# PROC010C_LP_Connector.net
KiCad netlist of a schematic drawn in Altium Designer
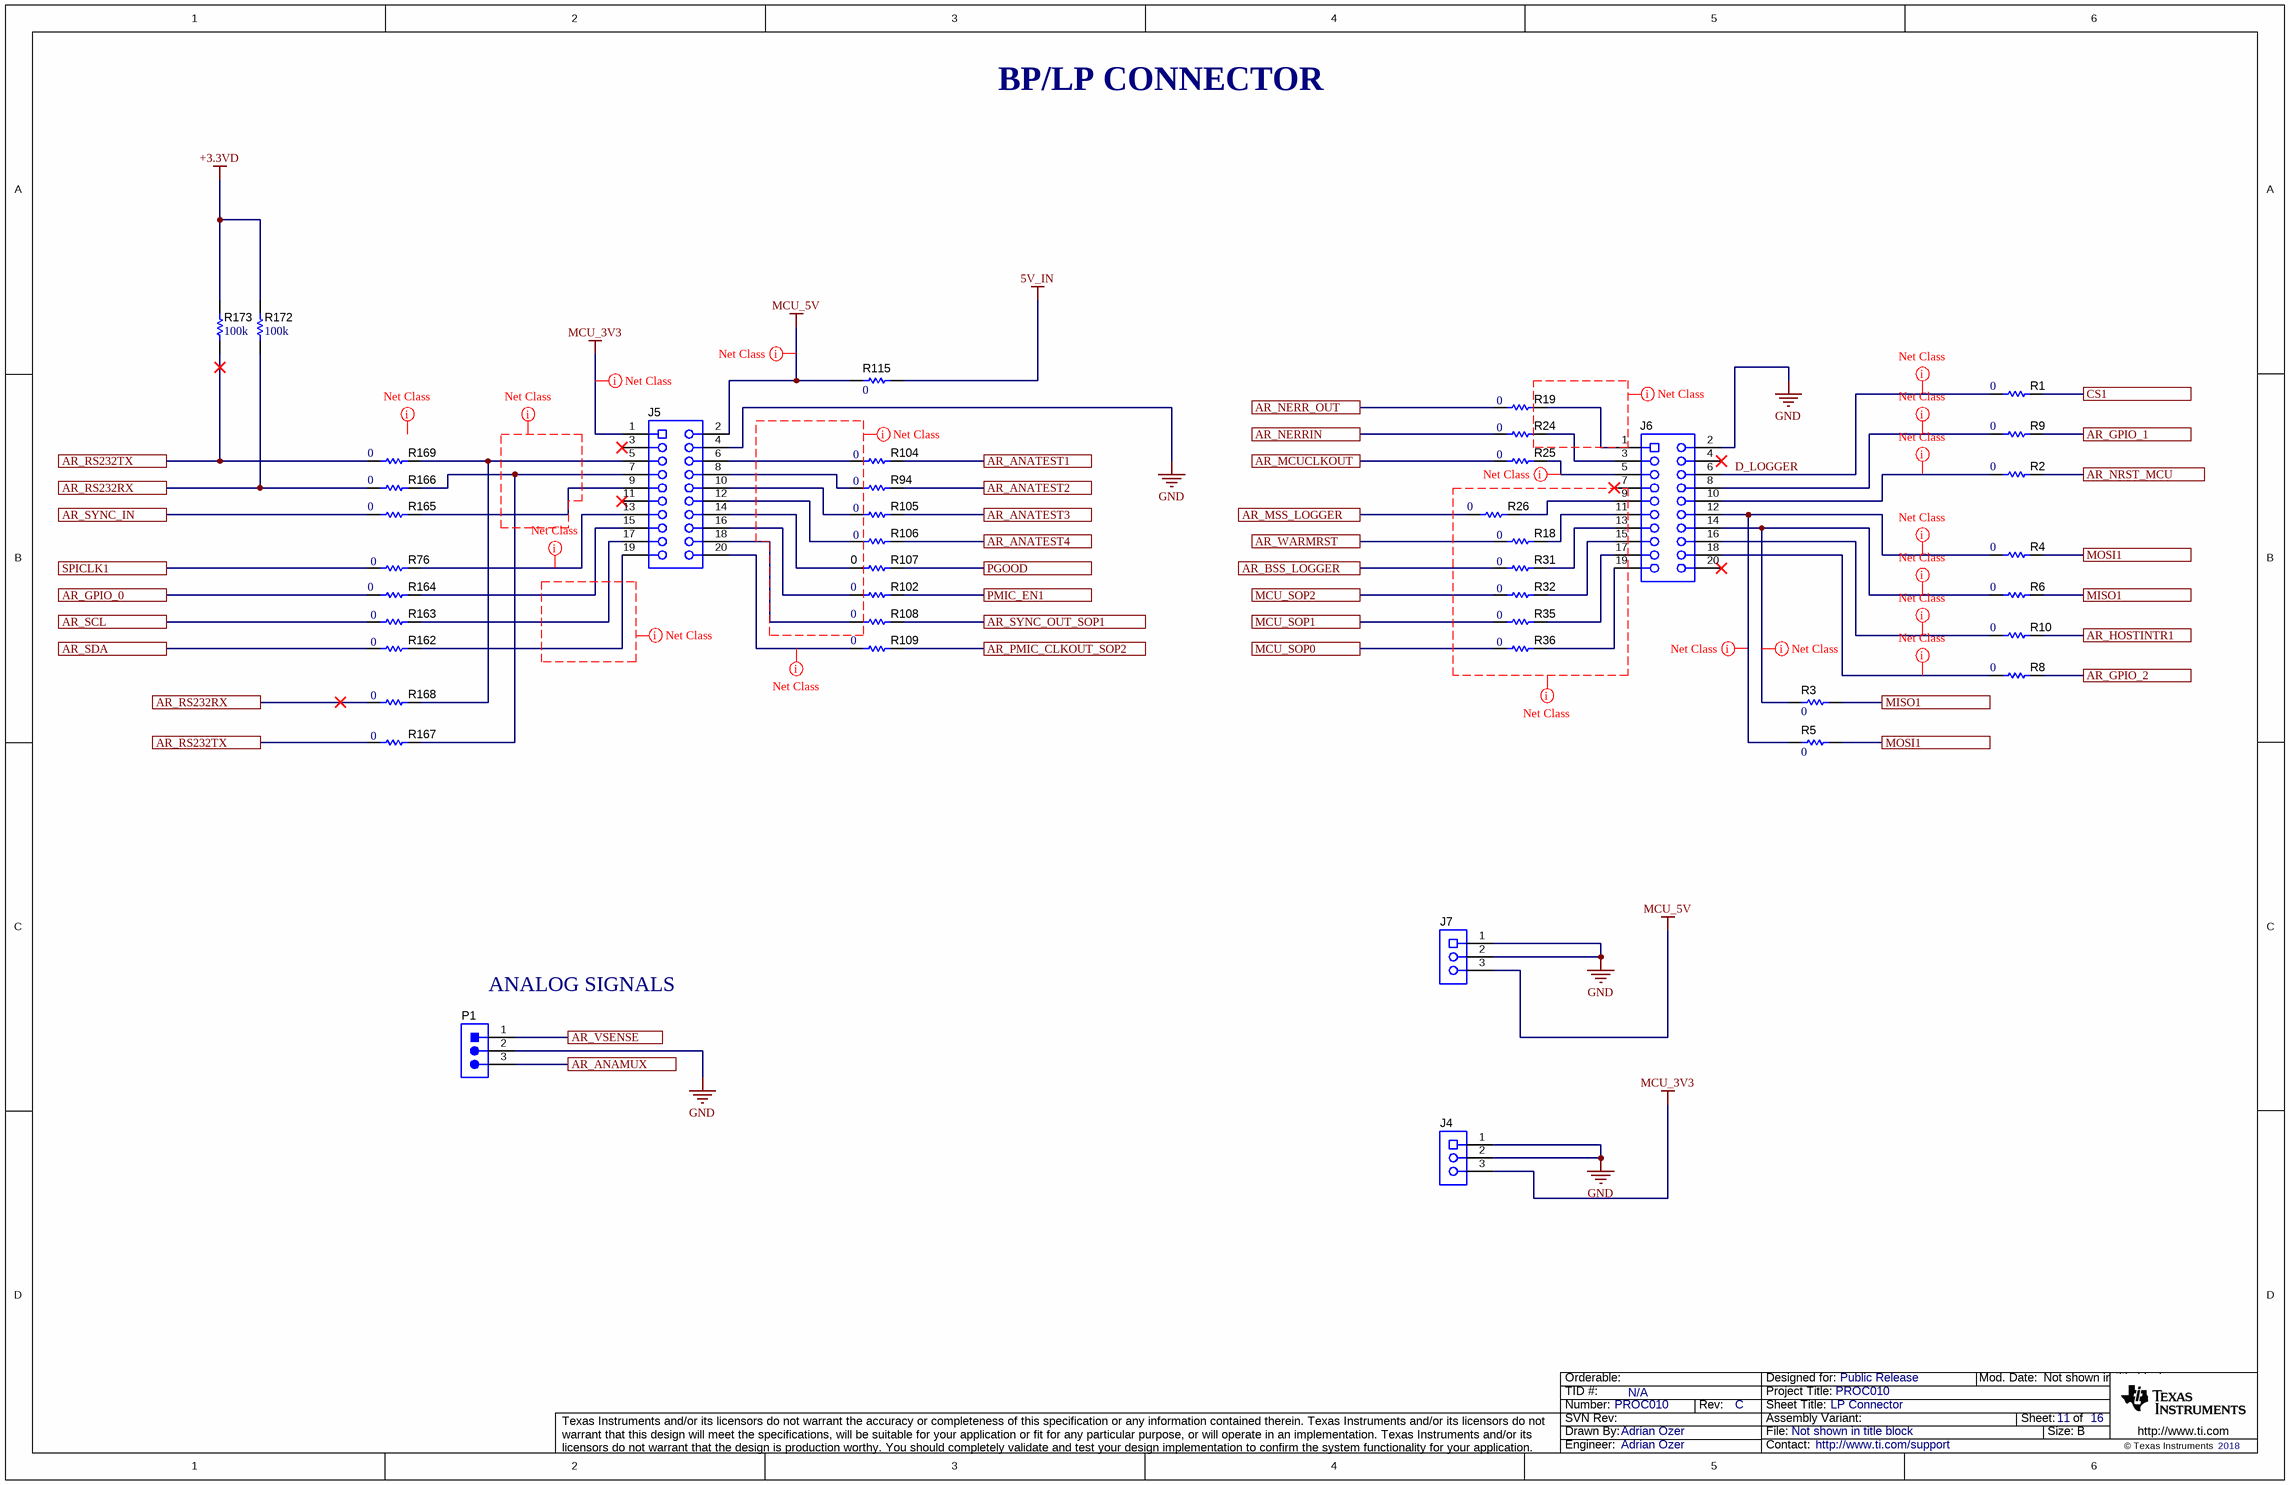
[diagram p0: PROC010C_LP Connector.SchDoc]

(export (version "E")
  (design (tool "Eeschema 10.0.6"))
  (components
    (comp (ref "J4")
      (value "SSM-103-S-SV")
      (footprint "Samtec_SSM-103-x-SV")
      (description "Receptacle, 2.54mm, 3x1, Gold with Tin tail, SMT")
      (fields (field (name "MANUFACTURER") "Samtec"))
      (libsource (lib "Altium Vault - TI") (part "CMP-0078183-1"))
    )
    (comp (ref "J5")
      (value "SSM-110-S-DV")
      (footprint "Samtec_SSM-110-x-DV")
      (description "Receptacle, 2.54mm, 10x2, Gold with Tin tail, SMT")
      (fields (field (name "MANUFACTURER") "Samtec"))
      (libsource (lib "Altium Vault - TI") (part "CMP-0078182-1"))
    )
    (comp (ref "J6")
      (value "SSM-110-S-DV")
      (footprint "Samtec_SSM-110-x-DV")
      (description "Receptacle, 2.54mm, 10x2, Gold with Tin tail, SMT")
      (fields (field (name "MANUFACTURER") "Samtec"))
      (libsource (lib "Altium Vault - TI") (part "CMP-0078182-1"))
    )
    (comp (ref "J7")
      (value "SSM-103-S-SV")
      (footprint "Samtec_SSM-103-x-SV")
      (description "Receptacle, 2.54mm, 3x1, Gold with Tin tail, SMT")
      (fields (field (name "MANUFACTURER") "Samtec"))
      (libsource (lib "Altium Vault - TI") (part "CMP-0078183-1"))
    )
    (comp (ref "P1")
      (value "TSW-103-07-T-S")
      (footprint "Samtec_TSW-103-07-T-S")
      (description "Header, 2.54 mm, 3x1, Tin, TH")
      (fields (field (name "MANUFACTURER") "Samtec"))
      (libsource (lib "Altium Vault - TI") (part "Header_3x1"))
    )
    (comp (ref "R1")
      (value "CRCW02010000Z0ED")
      (footprint "0201_Silk")
      (description "RES, 0, 5%, 0.05 W, 0201")
      (fields (field (name "MANUFACTURER") "Vishay-Dale") (field (name "VALUEDISPLAYED") "0"))
      (libsource (lib "Altium Vault - TI") (part "Resistor"))
    )
    (comp (ref "R2")
      (value "CRCW02010000Z0ED")
      (footprint "0201_Silk")
      (description "RES, 0, 5%, 0.05 W, 0201")
      (fields (field (name "MANUFACTURER") "Vishay-Dale") (field (name "VALUEDISPLAYED") "0"))
      (libsource (lib "Altium Vault - TI") (part "Resistor"))
    )
    (comp (ref "R3")
      (value "CRCW02010000Z0ED")
      (footprint "0201_Silk")
      (description "RES, 0, 5%, 0.05 W, 0201")
      (fields (field (name "MANUFACTURER") "Vishay-Dale") (field (name "VALUEDISPLAYED") "0"))
      (libsource (lib "Altium Vault - TI") (part "Resistor"))
    )
    (comp (ref "R4")
      (value "CRCW02010000Z0ED")
      (footprint "0201_Silk")
      (description "RES, 0, 5%, 0.05 W, 0201")
      (fields (field (name "MANUFACTURER") "Vishay-Dale") (field (name "VALUEDISPLAYED") "0"))
      (libsource (lib "Altium Vault - TI") (part "Resistor"))
    )
    (comp (ref "R5")
      (value "CRCW02010000Z0ED")
      (footprint "0201_Silk")
      (description "RES, 0, 5%, 0.05 W, 0201")
      (fields (field (name "MANUFACTURER") "Vishay-Dale") (field (name "VALUEDISPLAYED") "0"))
      (libsource (lib "Altium Vault - TI") (part "Resistor"))
    )
    (comp (ref "R6")
      (value "CRCW02010000Z0ED")
      (footprint "0201_Silk")
      (description "RES, 0, 5%, 0.05 W, 0201")
      (fields (field (name "MANUFACTURER") "Vishay-Dale") (field (name "VALUEDISPLAYED") "0"))
      (libsource (lib "Altium Vault - TI") (part "Resistor"))
    )
    (comp (ref "R8")
      (value "CRCW02010000Z0ED")
      (footprint "0201_Silk")
      (description "RES, 0, 5%, 0.05 W, 0201")
      (fields (field (name "MANUFACTURER") "Vishay-Dale") (field (name "VALUEDISPLAYED") "0"))
      (libsource (lib "Altium Vault - TI") (part "Resistor"))
    )
    (comp (ref "R9")
      (value "CRCW02010000Z0ED")
      (footprint "0201_Silk")
      (description "RES, 0, 5%, 0.05 W, 0201")
      (fields (field (name "MANUFACTURER") "Vishay-Dale") (field (name "VALUEDISPLAYED") "0"))
      (libsource (lib "Altium Vault - TI") (part "Resistor"))
    )
    (comp (ref "R10")
      (value "CRCW02010000Z0ED")
      (footprint "0201_Silk")
      (description "RES, 0, 5%, 0.05 W, 0201")
      (fields (field (name "MANUFACTURER") "Vishay-Dale") (field (name "VALUEDISPLAYED") "0"))
      (libsource (lib "Altium Vault - TI") (part "Resistor"))
    )
    (comp (ref "R18")
      (value "CRCW02010000Z0ED")
      (footprint "0201_Silk")
      (description "RES, 0, 5%, 0.05 W, 0201")
      (fields (field (name "MANUFACTURER") "Vishay-Dale") (field (name "VALUEDISPLAYED") "0"))
      (libsource (lib "Altium Vault - TI") (part "Resistor"))
    )
    (comp (ref "R19")
      (value "CRCW02010000Z0ED")
      (footprint "0201_Silk")
      (description "RES, 0, 5%, 0.05 W, 0201")
      (fields (field (name "MANUFACTURER") "Vishay-Dale") (field (name "VALUEDISPLAYED") "0"))
      (libsource (lib "Altium Vault - TI") (part "Resistor"))
    )
    (comp (ref "R24")
      (value "CRCW02010000Z0ED")
      (footprint "0201_Silk")
      (description "RES, 0, 5%, 0.05 W, 0201")
      (fields (field (name "MANUFACTURER") "Vishay-Dale") (field (name "VALUEDISPLAYED") "0"))
      (libsource (lib "Altium Vault - TI") (part "Resistor"))
    )
    (comp (ref "R25")
      (value "CRCW02010000Z0ED")
      (footprint "0201_Silk")
      (description "RES, 0, 5%, 0.05 W, 0201")
      (fields (field (name "MANUFACTURER") "Vishay-Dale") (field (name "VALUEDISPLAYED") "0"))
      (libsource (lib "Altium Vault - TI") (part "Resistor"))
    )
    (comp (ref "R26")
      (value "CRCW02010000Z0ED")
      (footprint "0201_Silk")
      (description "RES, 0, 5%, 0.05 W, 0201")
      (fields (field (name "MANUFACTURER") "Vishay-Dale") (field (name "VALUEDISPLAYED") "0"))
      (libsource (lib "Altium Vault - TI") (part "Resistor"))
    )
    (comp (ref "R31")
      (value "CRCW02010000Z0ED")
      (footprint "0201_Silk")
      (description "RES, 0, 5%, 0.05 W, 0201")
      (fields (field (name "MANUFACTURER") "Vishay-Dale") (field (name "VALUEDISPLAYED") "0"))
      (libsource (lib "Altium Vault - TI") (part "Resistor"))
    )
    (comp (ref "R32")
      (value "CRCW02010000Z0ED")
      (footprint "0201_Silk")
      (description "RES, 0, 5%, 0.05 W, 0201")
      (fields (field (name "MANUFACTURER") "Vishay-Dale") (field (name "VALUEDISPLAYED") "0"))
      (libsource (lib "Altium Vault - TI") (part "Resistor"))
    )
    (comp (ref "R35")
      (value "CRCW02010000Z0ED")
      (footprint "0201_Silk")
      (description "RES, 0, 5%, 0.05 W, 0201")
      (fields (field (name "MANUFACTURER") "Vishay-Dale") (field (name "VALUEDISPLAYED") "0"))
      (libsource (lib "Altium Vault - TI") (part "Resistor"))
    )
    (comp (ref "R36")
      (value "CRCW02010000Z0ED")
      (footprint "0201_Silk")
      (description "RES, 0, 5%, 0.05 W, 0201")
      (fields (field (name "MANUFACTURER") "Vishay-Dale") (field (name "VALUEDISPLAYED") "0"))
      (libsource (lib "Altium Vault - TI") (part "Resistor"))
    )
    (comp (ref "R76")
      (value "CRCW02010000Z0ED")
      (footprint "0201_Silk")
      (description "RES, 0, 5%, 0.05 W, 0201")
      (fields (field (name "MANUFACTURER") "Vishay-Dale") (field (name "VALUEDISPLAYED") "0"))
      (libsource (lib "Altium Vault - TI") (part "CMP-0027008-4"))
    )
    (comp (ref "R94")
      (value "CRCW02010000Z0ED")
      (footprint "0201_Silk")
      (description "RES, 0, 5%, 0.05 W, 0201")
      (fields (field (name "MANUFACTURER") "Vishay-Dale") (field (name "VALUEDISPLAYED") "0"))
      (libsource (lib "Altium Vault - TI") (part "Resistor"))
    )
    (comp (ref "R102")
      (value "CRCW02010000Z0ED")
      (footprint "0201_Silk")
      (description "RES, 0, 5%, 0.05 W, 0201")
      (fields (field (name "MANUFACTURER") "Vishay-Dale") (field (name "VALUEDISPLAYED") "0"))
      (libsource (lib "Altium Vault - TI") (part "Resistor"))
    )
    (comp (ref "R104")
      (value "CRCW02010000Z0ED")
      (footprint "0201_Silk")
      (description "RES, 0, 5%, 0.05 W, 0201")
      (fields (field (name "MANUFACTURER") "Vishay-Dale") (field (name "VALUEDISPLAYED") "0"))
      (libsource (lib "Altium Vault - TI") (part "CMP-0027008-4"))
    )
    (comp (ref "R105")
      (value "CRCW02010000Z0ED")
      (footprint "0201_Silk")
      (description "RES, 0, 5%, 0.05 W, 0201")
      (fields (field (name "MANUFACTURER") "Vishay-Dale") (field (name "VALUEDISPLAYED") "0"))
      (libsource (lib "Altium Vault - TI") (part "Resistor"))
    )
    (comp (ref "R106")
      (value "CRCW02010000Z0ED")
      (footprint "0201_Silk")
      (description "RES, 0, 5%, 0.05 W, 0201")
      (fields (field (name "MANUFACTURER") "Vishay-Dale") (field (name "VALUEDISPLAYED") "0"))
      (libsource (lib "Altium Vault - TI") (part "Resistor"))
    )
    (comp (ref "R107")
      (value "ERJ-2GE0R00X")
      (footprint "0402L")
      (description "RES, 0, 5%, 0.063 W, 0402")
      (fields
        (field (name "MANUFACTURER") "Panasonic")
        (field (name "VALUEDISPLAYED") "0")
        (field (name "PUBLISHER") "Texas Instruments")
      )
      (libsource (lib "Altium Vault - TI") (part "Resistor"))
    )
    (comp (ref "R108")
      (value "CRCW02010000Z0ED")
      (footprint "0201_Silk")
      (description "RES, 0, 5%, 0.05 W, 0201")
      (fields (field (name "MANUFACTURER") "Vishay-Dale") (field (name "VALUEDISPLAYED") "0"))
      (libsource (lib "Altium Vault - TI") (part "Resistor"))
    )
    (comp (ref "R109")
      (value "CRCW02010000Z0ED")
      (footprint "0201_Silk")
      (description "RES, 0, 5%, 0.05 W, 0201")
      (fields (field (name "MANUFACTURER") "Vishay-Dale") (field (name "VALUEDISPLAYED") "0"))
      (libsource (lib "Altium Vault - TI") (part "Resistor"))
    )
    (comp (ref "R115")
      (value "CRCW20100000Z0EF")
      (footprint "2010")
      (description "RES, 0, 5%, 0.75 W, AEC-Q200 Grade 0, 2010")
      (fields (field (name "MANUFACTURER") "Vishay-Dale") (field (name "VALUEDISPLAYED") "0"))
      (libsource (lib "Altium Vault - TI") (part "Resistor"))
    )
    (comp (ref "R162")
      (value "CRCW02010000Z0ED")
      (footprint "0201_Silk")
      (description "RES, 0, 5%, 0.05 W, 0201")
      (fields (field (name "MANUFACTURER") "Vishay-Dale") (field (name "VALUEDISPLAYED") "0"))
      (libsource (lib "Altium Vault - TI") (part "Resistor"))
    )
    (comp (ref "R163")
      (value "CRCW02010000Z0ED")
      (footprint "0201_Silk")
      (description "RES, 0, 5%, 0.05 W, 0201")
      (fields (field (name "MANUFACTURER") "Vishay-Dale") (field (name "VALUEDISPLAYED") "0"))
      (libsource (lib "Altium Vault - TI") (part "Resistor"))
    )
    (comp (ref "R164")
      (value "CRCW02010000Z0ED")
      (footprint "0201_Silk")
      (description "RES, 0, 5%, 0.05 W, 0201")
      (fields (field (name "MANUFACTURER") "Vishay-Dale") (field (name "VALUEDISPLAYED") "0"))
      (libsource (lib "Altium Vault - TI") (part "Resistor"))
    )
    (comp (ref "R165")
      (value "CRCW02010000Z0ED")
      (footprint "0201_Silk")
      (description "RES, 0, 5%, 0.05 W, 0201")
      (fields (field (name "MANUFACTURER") "Vishay-Dale") (field (name "VALUEDISPLAYED") "0"))
      (libsource (lib "Altium Vault - TI") (part "Resistor"))
    )
    (comp (ref "R166")
      (value "CRCW02010000Z0ED")
      (footprint "0201_Silk")
      (description "RES, 0, 5%, 0.05 W, 0201")
      (fields (field (name "MANUFACTURER") "Vishay-Dale") (field (name "VALUEDISPLAYED") "0"))
      (libsource (lib "Altium Vault - TI") (part "Resistor"))
    )
    (comp (ref "R167")
      (value "CRCW02010000Z0ED")
      (footprint "0201_Silk")
      (description "RES, 0, 5%, 0.05 W, 0201")
      (fields (field (name "MANUFACTURER") "Vishay-Dale") (field (name "VALUEDISPLAYED") "0"))
      (libsource (lib "Altium Vault - TI") (part "Resistor"))
    )
    (comp (ref "R168")
      (value "CRCW02010000Z0ED")
      (footprint "0201_Silk")
      (description "RES, 0, 5%, 0.05 W, 0201")
      (fields (field (name "MANUFACTURER") "Vishay-Dale") (field (name "VALUEDISPLAYED") "0"))
      (libsource (lib "Altium Vault - TI") (part "Resistor"))
    )
    (comp (ref "R169")
      (value "CRCW02010000Z0ED")
      (footprint "0201_Silk")
      (description "RES, 0, 5%, 0.05 W, 0201")
      (fields (field (name "MANUFACTURER") "Vishay-Dale") (field (name "VALUEDISPLAYED") "0"))
      (libsource (lib "Altium Vault - TI") (part "Resistor"))
    )
    (comp (ref "R172")
      (value "CRCW0402100KFKED")
      (footprint "0402L")
      (description "RES, 100 k, 1%, 0.063 W, AEC-Q200 Grade 0, 0402")
      (fields (field (name "MANUFACTURER") "Vishay-Dale") (field (name "VALUEDISPLAYED") "100k"))
      (libsource (lib "Altium Vault - TI") (part "Resistor"))
    )
    (comp (ref "R173")
      (value "CRCW0402100KFKED")
      (footprint "0402L")
      (description "RES, 100 k, 1%, 0.063 W, AEC-Q200 Grade 0, 0402")
      (fields (field (name "MANUFACTURER") "Vishay-Dale") (field (name "VALUEDISPLAYED") "100k"))
      (libsource (lib "Altium Vault - TI") (part "Resistor"))
    )
  )
  (nets
    (net (code "1") (name "+3.3VD") (class "Default")
      (node (ref "R172") (pin "2") (pinfunction "2_2") (pintype "passive"))
      (node (ref "R173") (pin "2") (pinfunction "2_2") (pintype "passive"))
    )
    (net (code "2") (name "/AR_ANAMUX") (class "Default")
      (node (ref "P1") (pin "3") (pinfunction "3_3") (pintype "passive"))
    )
    (net (code "3") (name "/AR_ANATEST1") (class "Default")
      (node (ref "R104") (pin "2") (pinfunction "2_2") (pintype "passive"))
    )
    (net (code "4") (name "/AR_ANATEST2") (class "Default")
      (node (ref "R94") (pin "2") (pinfunction "2_2") (pintype "passive"))
    )
    (net (code "5") (name "/AR_ANATEST3") (class "Default")
      (node (ref "R105") (pin "2") (pinfunction "2_2") (pintype "passive"))
    )
    (net (code "6") (name "/AR_ANATEST4") (class "Default")
      (node (ref "R106") (pin "2") (pinfunction "2_2") (pintype "passive"))
    )
    (net (code "7") (name "/AR_BSS_LOGGER") (class "Default")
      (node (ref "R31") (pin "1") (pinfunction "1_1") (pintype "passive"))
    )
    (net (code "8") (name "/AR_GPIO_0") (class "Default")
      (node (ref "R164") (pin "1") (pinfunction "1_1") (pintype "passive"))
    )
    (net (code "9") (name "/AR_GPIO_1") (class "Default")
      (node (ref "R9") (pin "2") (pinfunction "2_2") (pintype "passive"))
    )
    (net (code "10") (name "/AR_GPIO_2") (class "Default")
      (node (ref "R8") (pin "2") (pinfunction "2_2") (pintype "passive"))
    )
    (net (code "11") (name "/AR_HOSTINTR1") (class "Default")
      (node (ref "R10") (pin "2") (pinfunction "2_2") (pintype "passive"))
    )
    (net (code "12") (name "/AR_MCUCLKOUT") (class "Default")
      (node (ref "R25") (pin "1") (pinfunction "1_1") (pintype "passive"))
    )
    (net (code "13") (name "/AR_MSS_LOGGER") (class "Default")
      (node (ref "R26") (pin "1") (pinfunction "1_1") (pintype "passive"))
    )
    (net (code "14") (name "/AR_NERRIN") (class "Default")
      (node (ref "R24") (pin "1") (pinfunction "1_1") (pintype "passive"))
    )
    (net (code "15") (name "/AR_NERR_OUT") (class "Default")
      (node (ref "R19") (pin "1") (pinfunction "1_1") (pintype "passive"))
    )
    (net (code "16") (name "/AR_NRST_MCU") (class "Default")
      (node (ref "R2") (pin "2") (pinfunction "2_2") (pintype "passive"))
    )
    (net (code "17") (name "/AR_PMIC_CLKOUT_SOP2") (class "Default")
      (node (ref "R109") (pin "2") (pinfunction "2_2") (pintype "passive"))
    )
    (net (code "18") (name "/AR_RS232RX") (class "Default")
      (node (ref "R166") (pin "1") (pinfunction "1_1") (pintype "passive"))
      (node (ref "R168") (pin "1") (pinfunction "1_1") (pintype "passive"))
      (node (ref "R172") (pin "1") (pinfunction "1_1") (pintype "passive"))
    )
    (net (code "19") (name "/AR_RS232TX") (class "Default")
      (node (ref "R167") (pin "1") (pinfunction "1_1") (pintype "passive"))
      (node (ref "R169") (pin "1") (pinfunction "1_1") (pintype "passive"))
      (node (ref "R173") (pin "1") (pinfunction "1_1") (pintype "passive"))
    )
    (net (code "20") (name "/AR_SCL") (class "Default")
      (node (ref "R163") (pin "1") (pinfunction "1_1") (pintype "passive"))
    )
    (net (code "21") (name "/AR_SDA") (class "Default")
      (node (ref "R162") (pin "1") (pinfunction "1_1") (pintype "passive"))
    )
    (net (code "22") (name "/AR_SYNC_IN") (class "Default")
      (node (ref "R165") (pin "1") (pinfunction "1_1") (pintype "passive"))
    )
    (net (code "23") (name "/AR_SYNC_OUT_SOP1") (class "Default")
      (node (ref "R108") (pin "2") (pinfunction "2_2") (pintype "passive"))
    )
    (net (code "24") (name "/AR_VSENSE") (class "Default")
      (node (ref "P1") (pin "1") (pinfunction "1_1") (pintype "passive"))
    )
    (net (code "25") (name "/AR_WARMRST") (class "Default")
      (node (ref "R18") (pin "1") (pinfunction "1_1") (pintype "passive"))
    )
    (net (code "26") (name "/CS1") (class "Default")
      (node (ref "R1") (pin "2") (pinfunction "2_2") (pintype "passive"))
    )
    (net (code "27") (name "/D_LOGGER") (class "Default")
      (node (ref "J6") (pin "6") (pinfunction "6_6") (pintype "passive"))
      (node (ref "R1") (pin "1") (pinfunction "1_1") (pintype "passive"))
    )
    (net (code "28") (name "/MCU_SOP0") (class "Default")
      (node (ref "R36") (pin "1") (pinfunction "1_1") (pintype "passive"))
    )
    (net (code "29") (name "/MCU_SOP1") (class "Default")
      (node (ref "R35") (pin "1") (pinfunction "1_1") (pintype "passive"))
    )
    (net (code "30") (name "/MCU_SOP2") (class "Default")
      (node (ref "R32") (pin "1") (pinfunction "1_1") (pintype "passive"))
    )
    (net (code "31") (name "/MISO1") (class "Default")
      (node (ref "R3") (pin "2") (pinfunction "2_2") (pintype "passive"))
      (node (ref "R6") (pin "2") (pinfunction "2_2") (pintype "passive"))
    )
    (net (code "32") (name "/MOSI1") (class "Default")
      (node (ref "R4") (pin "2") (pinfunction "2_2") (pintype "passive"))
      (node (ref "R5") (pin "2") (pinfunction "2_2") (pintype "passive"))
    )
    (net (code "33") (name "/PGOOD") (class "Default")
      (node (ref "R107") (pin "2") (pinfunction "2_2") (pintype "passive"))
    )
    (net (code "34") (name "/PMIC_EN1") (class "Default")
      (node (ref "R102") (pin "2") (pinfunction "2_2") (pintype "passive"))
    )
    (net (code "35") (name "/SPICLK1") (class "Default")
      (node (ref "R76") (pin "1") (pinfunction "1_1") (pintype "passive"))
    )
    (net (code "36") (name "5V_IN") (class "Default")
      (node (ref "R115") (pin "2") (pinfunction "2_2") (pintype "passive"))
    )
    (net (code "37") (name "GND") (class "Default")
      (node (ref "J4") (pin "1") (pinfunction "1_1") (pintype "passive"))
      (node (ref "J4") (pin "2") (pinfunction "2_2") (pintype "passive"))
      (node (ref "J5") (pin "4") (pinfunction "4_4") (pintype "passive"))
      (node (ref "J6") (pin "2") (pinfunction "2_2") (pintype "passive"))
      (node (ref "J7") (pin "1") (pinfunction "1_1") (pintype "passive"))
      (node (ref "J7") (pin "2") (pinfunction "2_2") (pintype "passive"))
      (node (ref "P1") (pin "2") (pinfunction "2_2") (pintype "passive"))
    )
    (net (code "38") (name "MCU_3V3") (class "Default")
      (node (ref "J4") (pin "3") (pinfunction "3_3") (pintype "passive"))
      (node (ref "J5") (pin "1") (pinfunction "1_1") (pintype "passive"))
    )
    (net (code "39") (name "MCU_5V") (class "Default")
      (node (ref "J5") (pin "2") (pinfunction "2_2") (pintype "passive"))
      (node (ref "J7") (pin "3") (pinfunction "3_3") (pintype "passive"))
      (node (ref "R115") (pin "1") (pinfunction "1_1") (pintype "passive"))
    )
    (net (code "40") (name "Net-(J5-Pad5)") (class "Default")
      (node (ref "J5") (pin "5") (pinfunction "5_5") (pintype "passive"))
      (node (ref "R168") (pin "2") (pinfunction "2_2") (pintype "passive"))
      (node (ref "R169") (pin "2") (pinfunction "2_2") (pintype "passive"))
    )
    (net (code "41") (name "Net-(J5-Pad6)") (class "Default")
      (node (ref "J5") (pin "6") (pinfunction "6_6") (pintype "passive"))
      (node (ref "R104") (pin "1") (pinfunction "1_1") (pintype "passive"))
    )
    (net (code "42") (name "Net-(J5-Pad7)") (class "Default")
      (node (ref "J5") (pin "7") (pinfunction "7_7") (pintype "passive"))
      (node (ref "R166") (pin "2") (pinfunction "2_2") (pintype "passive"))
      (node (ref "R167") (pin "2") (pinfunction "2_2") (pintype "passive"))
    )
    (net (code "43") (name "Net-(J5-Pad8)") (class "Default")
      (node (ref "J5") (pin "8") (pinfunction "8_8") (pintype "passive"))
      (node (ref "R94") (pin "1") (pinfunction "1_1") (pintype "passive"))
    )
    (net (code "44") (name "Net-(J5-Pad9)") (class "Default")
      (node (ref "J5") (pin "9") (pinfunction "9_9") (pintype "passive"))
      (node (ref "R165") (pin "2") (pinfunction "2_2") (pintype "passive"))
    )
    (net (code "45") (name "Net-(J5-Pad10)") (class "Default")
      (node (ref "J5") (pin "10") (pinfunction "10_10") (pintype "passive"))
      (node (ref "R105") (pin "1") (pinfunction "1_1") (pintype "passive"))
    )
    (net (code "46") (name "Net-(J5-Pad12)") (class "Default")
      (node (ref "J5") (pin "12") (pinfunction "12_12") (pintype "passive"))
      (node (ref "R106") (pin "1") (pinfunction "1_1") (pintype "passive"))
    )
    (net (code "47") (name "Net-(J5-Pad13)") (class "Default")
      (node (ref "J5") (pin "13") (pinfunction "13_13") (pintype "passive"))
      (node (ref "R76") (pin "2") (pinfunction "2_2") (pintype "passive"))
    )
    (net (code "48") (name "Net-(J5-Pad14)") (class "Default")
      (node (ref "J5") (pin "14") (pinfunction "14_14") (pintype "passive"))
      (node (ref "R107") (pin "1") (pinfunction "1_1") (pintype "passive"))
    )
    (net (code "49") (name "Net-(J5-Pad15)") (class "Default")
      (node (ref "J5") (pin "15") (pinfunction "15_15") (pintype "passive"))
      (node (ref "R164") (pin "2") (pinfunction "2_2") (pintype "passive"))
    )
    (net (code "50") (name "Net-(J5-Pad16)") (class "Default")
      (node (ref "J5") (pin "16") (pinfunction "16_16") (pintype "passive"))
      (node (ref "R102") (pin "1") (pinfunction "1_1") (pintype "passive"))
    )
    (net (code "51") (name "Net-(J5-Pad17)") (class "Default")
      (node (ref "J5") (pin "17") (pinfunction "17_17") (pintype "passive"))
      (node (ref "R163") (pin "2") (pinfunction "2_2") (pintype "passive"))
    )
    (net (code "52") (name "Net-(J5-Pad18)") (class "Default")
      (node (ref "J5") (pin "18") (pinfunction "18_18") (pintype "passive"))
      (node (ref "R108") (pin "1") (pinfunction "1_1") (pintype "passive"))
    )
    (net (code "53") (name "Net-(J5-Pad19)") (class "Default")
      (node (ref "J5") (pin "19") (pinfunction "19_19") (pintype "passive"))
      (node (ref "R162") (pin "2") (pinfunction "2_2") (pintype "passive"))
    )
    (net (code "54") (name "Net-(J5-Pad20)") (class "Default")
      (node (ref "J5") (pin "20") (pinfunction "20_20") (pintype "passive"))
      (node (ref "R109") (pin "1") (pinfunction "1_1") (pintype "passive"))
    )
    (net (code "55") (name "Net-(J6-Pad1)") (class "Default")
      (node (ref "J6") (pin "1") (pinfunction "1_1") (pintype "passive"))
      (node (ref "R19") (pin "2") (pinfunction "2_2") (pintype "passive"))
    )
    (net (code "56") (name "Net-(J6-Pad3)") (class "Default")
      (node (ref "J6") (pin "3") (pinfunction "3_3") (pintype "passive"))
      (node (ref "R24") (pin "2") (pinfunction "2_2") (pintype "passive"))
    )
    (net (code "57") (name "Net-(J6-Pad5)") (class "Default")
      (node (ref "J6") (pin "5") (pinfunction "5_5") (pintype "passive"))
      (node (ref "R25") (pin "2") (pinfunction "2_2") (pintype "passive"))
    )
    (net (code "58") (name "Net-(J6-Pad8)") (class "Default")
      (node (ref "J6") (pin "8") (pinfunction "8_8") (pintype "passive"))
      (node (ref "R9") (pin "1") (pinfunction "1_1") (pintype "passive"))
    )
    (net (code "59") (name "Net-(J6-Pad9)") (class "Default")
      (node (ref "J6") (pin "9") (pinfunction "9_9") (pintype "passive"))
      (node (ref "R26") (pin "2") (pinfunction "2_2") (pintype "passive"))
    )
    (net (code "60") (name "Net-(J6-Pad10)") (class "Default")
      (node (ref "J6") (pin "10") (pinfunction "10_10") (pintype "passive"))
      (node (ref "R2") (pin "1") (pinfunction "1_1") (pintype "passive"))
    )
    (net (code "61") (name "Net-(J6-Pad11)") (class "Default")
      (node (ref "J6") (pin "11") (pinfunction "11_11") (pintype "passive"))
      (node (ref "R18") (pin "2") (pinfunction "2_2") (pintype "passive"))
    )
    (net (code "62") (name "Net-(J6-Pad12)") (class "Default")
      (node (ref "J6") (pin "12") (pinfunction "12_12") (pintype "passive"))
      (node (ref "R4") (pin "1") (pinfunction "1_1") (pintype "passive"))
      (node (ref "R5") (pin "1") (pinfunction "1_1") (pintype "passive"))
    )
    (net (code "63") (name "Net-(J6-Pad13)") (class "Default")
      (node (ref "J6") (pin "13") (pinfunction "13_13") (pintype "passive"))
      (node (ref "R31") (pin "2") (pinfunction "2_2") (pintype "passive"))
    )
    (net (code "64") (name "Net-(J6-Pad14)") (class "Default")
      (node (ref "J6") (pin "14") (pinfunction "14_14") (pintype "passive"))
      (node (ref "R3") (pin "1") (pinfunction "1_1") (pintype "passive"))
      (node (ref "R6") (pin "1") (pinfunction "1_1") (pintype "passive"))
    )
    (net (code "65") (name "Net-(J6-Pad15)") (class "Default")
      (node (ref "J6") (pin "15") (pinfunction "15_15") (pintype "passive"))
      (node (ref "R32") (pin "2") (pinfunction "2_2") (pintype "passive"))
    )
    (net (code "66") (name "Net-(J6-Pad16)") (class "Default")
      (node (ref "J6") (pin "16") (pinfunction "16_16") (pintype "passive"))
      (node (ref "R10") (pin "1") (pinfunction "1_1") (pintype "passive"))
    )
    (net (code "67") (name "Net-(J6-Pad17)") (class "Default")
      (node (ref "J6") (pin "17") (pinfunction "17_17") (pintype "passive"))
      (node (ref "R35") (pin "2") (pinfunction "2_2") (pintype "passive"))
    )
    (net (code "68") (name "Net-(J6-Pad18)") (class "Default")
      (node (ref "J6") (pin "18") (pinfunction "18_18") (pintype "passive"))
      (node (ref "R8") (pin "1") (pinfunction "1_1") (pintype "passive"))
    )
    (net (code "69") (name "Net-(J6-Pad19)") (class "Default")
      (node (ref "J6") (pin "19") (pinfunction "19_19") (pintype "passive"))
      (node (ref "R36") (pin "2") (pinfunction "2_2") (pintype "passive"))
    )
    (net (code "70") (name "unconnected-(J5-Pad3)") (class "Default")
      (node (ref "J5") (pin "3") (pinfunction "3_3") (pintype "passive+no_connect"))
    )
    (net (code "71") (name "unconnected-(J5-Pad11)") (class "Default")
      (node (ref "J5") (pin "11") (pinfunction "11_11") (pintype "passive+no_connect"))
    )
    (net (code "72") (name "unconnected-(J6-Pad4)") (class "Default")
      (node (ref "J6") (pin "4") (pinfunction "4_4") (pintype "passive+no_connect"))
    )
    (net (code "73") (name "unconnected-(J6-Pad7)") (class "Default")
      (node (ref "J6") (pin "7") (pinfunction "7_7") (pintype "passive+no_connect"))
    )
    (net (code "74") (name "unconnected-(J6-Pad20)") (class "Default")
      (node (ref "J6") (pin "20") (pinfunction "20_20") (pintype "passive+no_connect"))
    )
  )
)
